# Motor_driver.net
KiCad netlist of a schematic drawn in Altium Designer
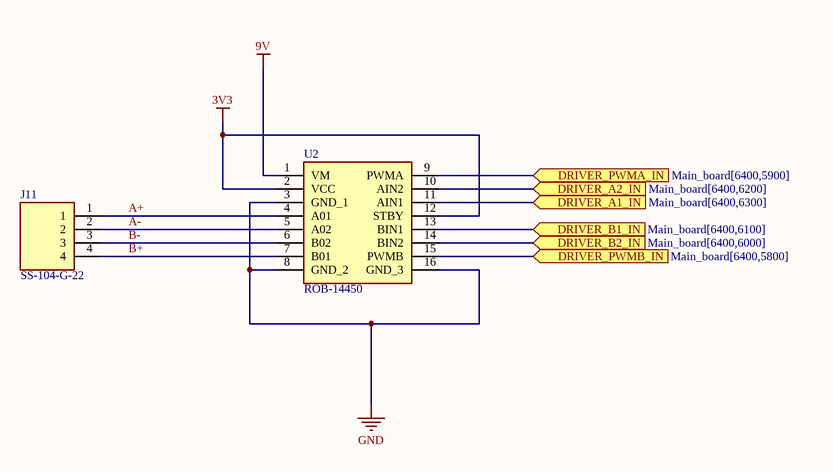
[diagram p0: Motor_driver.SchDoc]

(export (version "E")
  (design (tool "Eeschema 10.0.6"))
  (components
    (comp (ref "J11")
      (value "SS-104-G-22")
      (footprint "PCB 4 PIN PADS")
      (description "Connector")
      (libsource (lib "SamacSys") (part "SS-104-G-22"))
    )
    (comp (ref "U2")
      (value "ROB-14450")
      (footprint "SamacSys:ROB14450")
      (description "Undefined or Miscellaneous")
      (fields (field (name "MOUSER PART NUMBER") "474-ROB-14450"))
      (libsource (lib "*") (part "ROB-14450"))
    )
  )
  (nets
    (net (code "1") (name "/A+") (class "Default")
      (node (ref "J11") (pin "1") (pinfunction "1_1") (pintype "passive"))
      (node (ref "U2") (pin "4") (pinfunction "A01_4") (pintype "passive"))
    )
    (net (code "2") (name "/A-") (class "Default")
      (node (ref "J11") (pin "2") (pinfunction "2_2") (pintype "passive"))
      (node (ref "U2") (pin "5") (pinfunction "A02_5") (pintype "passive"))
    )
    (net (code "3") (name "/B+") (class "Default")
      (node (ref "J11") (pin "4") (pinfunction "4_4") (pintype "passive"))
      (node (ref "U2") (pin "7") (pinfunction "B01_7") (pintype "passive"))
    )
    (net (code "4") (name "/B-") (class "Default")
      (node (ref "J11") (pin "3") (pinfunction "3_3") (pintype "passive"))
      (node (ref "U2") (pin "6") (pinfunction "B02_6") (pintype "passive"))
    )
    (net (code "5") (name "/DRIVER_A1_IN") (class "Default")
      (node (ref "U2") (pin "11") (pinfunction "AIN1_11") (pintype "passive"))
    )
    (net (code "6") (name "/DRIVER_A2_IN") (class "Default")
      (node (ref "U2") (pin "10") (pinfunction "AIN2_10") (pintype "passive"))
    )
    (net (code "7") (name "/DRIVER_B1_IN") (class "Default")
      (node (ref "U2") (pin "13") (pinfunction "BIN1_13") (pintype "passive"))
    )
    (net (code "8") (name "/DRIVER_B2_IN") (class "Default")
      (node (ref "U2") (pin "14") (pinfunction "BIN2_14") (pintype "passive"))
    )
    (net (code "9") (name "/DRIVER_PWMA_IN") (class "Default")
      (node (ref "U2") (pin "9") (pinfunction "PWMA_9") (pintype "passive"))
    )
    (net (code "10") (name "/DRIVER_PWMB_IN") (class "Default")
      (node (ref "U2") (pin "15") (pinfunction "PWMB_15") (pintype "passive"))
    )
    (net (code "11") (name "3V3") (class "Default")
      (node (ref "U2") (pin "12") (pinfunction "STBY_12") (pintype "passive"))
      (node (ref "U2") (pin "2") (pinfunction "VCC_2") (pintype "passive"))
    )
    (net (code "12") (name "9V") (class "Default")
      (node (ref "U2") (pin "1") (pinfunction "VM_1") (pintype "passive"))
    )
    (net (code "13") (name "GND") (class "Default")
      (node (ref "U2") (pin "16") (pinfunction "GND_3_16") (pintype "passive"))
      (node (ref "U2") (pin "3") (pinfunction "GND_1_3") (pintype "passive"))
      (node (ref "U2") (pin "8") (pinfunction "GND_2_8") (pintype "passive"))
    )
  )
)
